# miniE_arduino_shield_v1-3.net
KiCad netlist of a schematic drawn in EAGLE
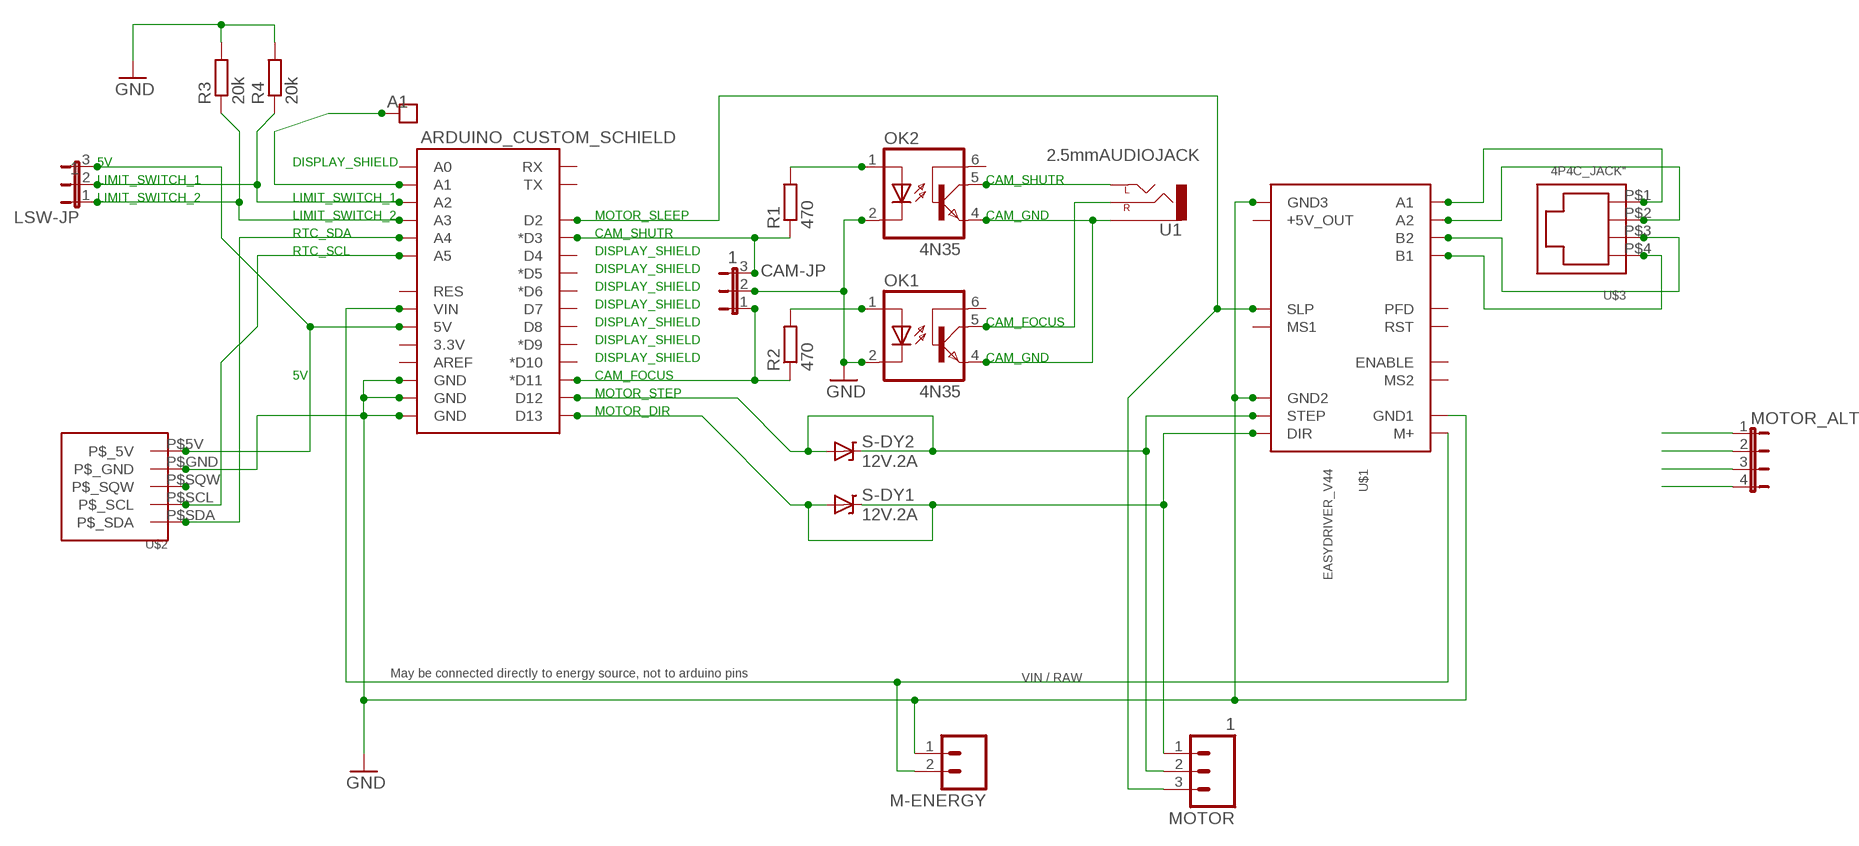
[diagram p0: schematic, sheet 1]

(export (version "E")
  (design (tool "Eeschema 10.0.6"))
  (components
    (comp (ref "ARDUINO_CUSTOM_SCHIELD")
      (value "ARDUINO_SHIELDNOLABELS")
      (footprint "eagle-import:DUEMILANOVE_SHIELD_NOLABELS")
      (libsource (lib "eagle-import") (part "ARDUINO_SHIELDNOLABELS"))
    )
    (comp (ref "CAM-JP")
      (value "1")
      (footprint "eagle-import:JP2")
      (libsource (lib "eagle-import") (part "JP2E"))
    )
    (comp (ref "LSW-JP")
      (value "1")
      (footprint "eagle-import:JP2")
      (libsource (lib "eagle-import") (part "JP2E"))
    )
    (comp (ref "M-ENERGY")
      (value "MOLEX_02")
      (footprint "eagle-import:1X02")
      (libsource (lib "eagle-import") (part "M02PTH"))
    )
    (comp (ref "MOTOR")
      (value "1")
      (footprint "eagle-import:1X03")
      (libsource (lib "eagle-import") (part "M03PTH"))
    )
    (comp (ref "MOTOR_ALT")
      (value "JP4E")
      (footprint "eagle-import:JP4")
      (libsource (lib "eagle-import") (part "JP4E"))
    )
    (comp (ref "OK1")
      (value "4N35")
      (footprint "eagle-import:DIL06")
      (fields (field (name "MF") "FAIRCHILD SEMICONDUCTOR"))
      (libsource (lib "eagle-import") (part "4N35"))
    )
    (comp (ref "OK2")
      (value "4N35")
      (footprint "eagle-import:DIL06")
      (fields (field (name "MF") "FAIRCHILD SEMICONDUCTOR"))
      (libsource (lib "eagle-import") (part "4N35"))
    )
    (comp (ref "R1")
      (value "470")
      (footprint "eagle-import:0207_10")
      (libsource (lib "eagle-import") (part "R-EU_0207/10"))
    )
    (comp (ref "R2")
      (value "470")
      (footprint "eagle-import:0207_10")
      (libsource (lib "eagle-import") (part "R-EU_0207/10"))
    )
    (comp (ref "R3")
      (value "20k")
      (footprint "eagle-import:0207_10")
      (libsource (lib "eagle-import") (part "R-EU_0207/10"))
    )
    (comp (ref "R4")
      (value "20k")
      (footprint "eagle-import:0207_10")
      (libsource (lib "eagle-import") (part "R-EU_0207/10"))
    )
    (comp (ref "S-DY1")
      (value "12V.2A")
      (footprint "eagle-import:DIODE-ZENER")
      (libsource (lib "eagle-import") (part "DIODE-ZENERPTH"))
    )
    (comp (ref "S-DY2")
      (value "12V.2A")
      (footprint "eagle-import:DIODE-ZENER")
      (libsource (lib "eagle-import") (part "DIODE-ZENERPTH"))
    )
    (comp (ref "U$1")
      (value "EASYDRIVER_V44")
      (footprint "eagle-import:EASYDRIVER_V44")
      (libsource (lib "eagle-import") (part "EASYDRIVER_V44"))
    )
    (comp (ref "U$2")
      (value "SPARKFUN_RTC_MODULE-OPTIONAL")
      (footprint "eagle-import:SPARKFUN_RTC_MODULE_OPTIONAL")
      (libsource (lib "eagle-import") (part "SPARKFUN_RTC_MODULE-OPTIONAL"))
    )
    (comp (ref "U$3")
      (value "4P4C_JACK\"")
      (footprint "eagle-import:4P4C_JACK-ASS-2004-3-4-LP-N-R")
      (libsource (lib "eagle-import") (part "4P4C_JACK{dblquote}"))
    )
    (comp (ref "U$4")
      (value "JUMPER_1X1")
      (footprint "eagle-import:JUMPER_1X1")
      (libsource (lib "eagle-import") (part "JUMPER_1X1"))
    )
    (comp (ref "U1")
      (value "2.5mmAUDIOJACK")
      (footprint "eagle-import:STEREOJACK2.5MM_STEREOJACK2.5MM")
      (libsource (lib "eagle-import") (part "AUDIO-JACK2.5MM"))
    )
  )
  (nets
    (net (code "1") (name "/A1") (class "Default")
      (node (ref "MOTOR_ALT") (pin "1") (pinfunction "1_1") (pintype "passive"))
      (node (ref "U$1") (pin "A1") (pinfunction "A1_A1") (pintype "bidirectional"))
      (node (ref "U$3") (pin "P$1") (pinfunction "P$1_P$1") (pintype "bidirectional"))
    )
    (net (code "2") (name "/A2") (class "Default")
      (node (ref "MOTOR_ALT") (pin "2") (pinfunction "2_2") (pintype "passive"))
      (node (ref "U$1") (pin "A2") (pinfunction "A2_A2") (pintype "bidirectional"))
      (node (ref "U$3") (pin "P$2") (pinfunction "P$2_P$2") (pintype "bidirectional"))
    )
    (net (code "3") (name "/B1") (class "Default")
      (node (ref "MOTOR_ALT") (pin "4") (pinfunction "4_4") (pintype "passive"))
      (node (ref "U$1") (pin "B1") (pinfunction "B1_B1") (pintype "bidirectional"))
      (node (ref "U$3") (pin "P$4") (pinfunction "P$4_P$4") (pintype "bidirectional"))
    )
    (net (code "4") (name "/B2") (class "Default")
      (node (ref "MOTOR_ALT") (pin "3") (pinfunction "3_3") (pintype "passive"))
      (node (ref "U$1") (pin "B2") (pinfunction "B2_B2") (pintype "bidirectional"))
      (node (ref "U$3") (pin "P$3") (pinfunction "P$3_P$3") (pintype "bidirectional"))
    )
    (net (code "5") (name "GND") (class "Default")
      (node (ref "ARDUINO_CUSTOM_SCHIELD") (pin "GND@0") (pinfunction "GND_GND@0") (pintype "bidirectional"))
      (node (ref "ARDUINO_CUSTOM_SCHIELD") (pin "GND@1") (pinfunction "GND_GND@1") (pintype "bidirectional"))
      (node (ref "ARDUINO_CUSTOM_SCHIELD") (pin "GND@2") (pinfunction "GND_GND@2") (pintype "bidirectional"))
      (node (ref "CAM-JP") (pin "2") (pinfunction "2_2") (pintype "passive"))
      (node (ref "M-ENERGY") (pin "1") (pinfunction "1_1") (pintype "passive"))
      (node (ref "OK1") (pin "2") (pinfunction "C_2") (pintype "passive"))
      (node (ref "OK2") (pin "2") (pinfunction "C_2") (pintype "passive"))
      (node (ref "R3") (pin "2") (pinfunction "2_2") (pintype "passive"))
      (node (ref "R4") (pin "2") (pinfunction "2_2") (pintype "passive"))
      (node (ref "U$1") (pin "GND1") (pinfunction "GND1_GND1") (pintype "bidirectional"))
      (node (ref "U$1") (pin "GND2") (pinfunction "GND2_GND2") (pintype "bidirectional"))
      (node (ref "U$1") (pin "GND3") (pinfunction "GND3_GND3") (pintype "bidirectional"))
      (node (ref "U$2") (pin "P$GND") (pinfunction "P$_GND_P$GND") (pintype "bidirectional"))
    )
    (net (code "6") (name "Net-(ARDUINO_CUSTOM_SCHIELD-*D3)") (class "Default")
      (node (ref "ARDUINO_CUSTOM_SCHIELD") (pin "D3") (pinfunction "*D3_D3") (pintype "bidirectional"))
      (node (ref "CAM-JP") (pin "3") (pinfunction "3_3") (pintype "passive"))
      (node (ref "R1") (pin "1") (pinfunction "1_1") (pintype "passive"))
    )
    (net (code "7") (name "Net-(ARDUINO_CUSTOM_SCHIELD-*D11)") (class "Default")
      (node (ref "ARDUINO_CUSTOM_SCHIELD") (pin "D11") (pinfunction "*D11_D11") (pintype "bidirectional"))
      (node (ref "CAM-JP") (pin "1") (pinfunction "1_1") (pintype "passive"))
      (node (ref "R2") (pin "1") (pinfunction "1_1") (pintype "passive"))
    )
    (net (code "8") (name "Net-(ARDUINO_CUSTOM_SCHIELD-PadA1)") (class "Default")
      (node (ref "ARDUINO_CUSTOM_SCHIELD") (pin "A1") (pinfunction "A1_A1") (pintype "bidirectional"))
      (node (ref "U$4") (pin "P$1") (pinfunction "P$1_P$1") (pintype "bidirectional"))
    )
    (net (code "9") (name "Net-(ARDUINO_CUSTOM_SCHIELD-PadA2)") (class "Default")
      (node (ref "ARDUINO_CUSTOM_SCHIELD") (pin "A2") (pinfunction "A2_A2") (pintype "bidirectional"))
      (node (ref "LSW-JP") (pin "2") (pinfunction "2_2") (pintype "passive"))
      (node (ref "R4") (pin "1") (pinfunction "1_1") (pintype "passive"))
    )
    (net (code "10") (name "Net-(ARDUINO_CUSTOM_SCHIELD-PadA3)") (class "Default")
      (node (ref "ARDUINO_CUSTOM_SCHIELD") (pin "A3") (pinfunction "A3_A3") (pintype "bidirectional"))
      (node (ref "LSW-JP") (pin "1") (pinfunction "1_1") (pintype "passive"))
      (node (ref "R3") (pin "1") (pinfunction "1_1") (pintype "passive"))
    )
    (net (code "11") (name "Net-(ARDUINO_CUSTOM_SCHIELD-PadVIN)") (class "Default")
      (node (ref "ARDUINO_CUSTOM_SCHIELD") (pin "VIN") (pinfunction "VIN_VIN") (pintype "bidirectional"))
      (node (ref "M-ENERGY") (pin "2") (pinfunction "2_2") (pintype "passive"))
      (node (ref "U$1") (pin "M+") (pinfunction "M+_M+") (pintype "bidirectional"))
    )
    (net (code "12") (name "Net-(OK1-A)") (class "Default")
      (node (ref "OK1") (pin "1") (pinfunction "A_1") (pintype "passive"))
      (node (ref "R2") (pin "2") (pinfunction "2_2") (pintype "passive"))
    )
    (net (code "13") (name "Net-(OK1-COL)") (class "Default")
      (node (ref "OK1") (pin "5") (pinfunction "COL_5") (pintype "passive"))
      (node (ref "U1") (pin "RING1") (pinfunction "RIGHT_RING1") (pintype "bidirectional"))
      (node (ref "U1") (pin "RING2") (pinfunction "RIGHT_RING2") (pintype "bidirectional"))
    )
    (net (code "14") (name "Net-(OK1-EMI)") (class "Default")
      (node (ref "OK1") (pin "4") (pinfunction "EMI_4") (pintype "passive"))
      (node (ref "OK2") (pin "4") (pinfunction "EMI_4") (pintype "passive"))
      (node (ref "U1") (pin "SLEEVE") (pinfunction "SLEEVE_SLEEVE") (pintype "bidirectional"))
    )
    (net (code "15") (name "Net-(OK2-A)") (class "Default")
      (node (ref "OK2") (pin "1") (pinfunction "A_1") (pintype "passive"))
      (node (ref "R1") (pin "2") (pinfunction "2_2") (pintype "passive"))
    )
    (net (code "16") (name "Net-(OK2-COL)") (class "Default")
      (node (ref "OK2") (pin "5") (pinfunction "COL_5") (pintype "passive"))
      (node (ref "U1") (pin "TIP") (pinfunction "LEFT_TIP") (pintype "bidirectional"))
    )
    (net (code "17") (name "Net-(S-DY1-A)") (class "Default")
      (node (ref "ARDUINO_CUSTOM_SCHIELD") (pin "D13") (pinfunction "D13_D13") (pintype "bidirectional"))
      (node (ref "MOTOR") (pin "1") (pinfunction "1_1") (pintype "passive"))
      (node (ref "S-DY1") (pin "P$1") (pinfunction "C_P$1") (pintype "passive"))
      (node (ref "S-DY1") (pin "P$2") (pinfunction "A_P$2") (pintype "passive"))
      (node (ref "U$1") (pin "DIR") (pinfunction "DIR_DIR") (pintype "bidirectional"))
    )
    (net (code "18") (name "Net-(S-DY2-A)") (class "Default")
      (node (ref "ARDUINO_CUSTOM_SCHIELD") (pin "D12") (pinfunction "D12_D12") (pintype "bidirectional"))
      (node (ref "MOTOR") (pin "2") (pinfunction "2_2") (pintype "passive"))
      (node (ref "S-DY2") (pin "P$1") (pinfunction "C_P$1") (pintype "passive"))
      (node (ref "S-DY2") (pin "P$2") (pinfunction "A_P$2") (pintype "passive"))
      (node (ref "U$1") (pin "STEP") (pinfunction "STEP_STEP") (pintype "bidirectional"))
    )
    (net (code "19") (name "Net-(U$1-SLP)") (class "Default")
      (node (ref "ARDUINO_CUSTOM_SCHIELD") (pin "D2") (pinfunction "D2_D2") (pintype "bidirectional"))
      (node (ref "MOTOR") (pin "3") (pinfunction "3_3") (pintype "passive"))
      (node (ref "U$1") (pin "SLEEP") (pinfunction "SLP_SLEEP") (pintype "bidirectional"))
    )
    (net (code "20") (name "Net-(U$2-P$_5V)") (class "Default")
      (node (ref "ARDUINO_CUSTOM_SCHIELD") (pin "5V") (pinfunction "5V_5V") (pintype "bidirectional"))
      (node (ref "LSW-JP") (pin "3") (pinfunction "3_3") (pintype "passive"))
      (node (ref "U$2") (pin "P$5V") (pinfunction "P$_5V_P$5V") (pintype "bidirectional"))
    )
    (net (code "21") (name "Net-(U$2-P$_SCL)") (class "Default")
      (node (ref "ARDUINO_CUSTOM_SCHIELD") (pin "A5") (pinfunction "A5_A5") (pintype "bidirectional"))
      (node (ref "U$2") (pin "P$SCL") (pinfunction "P$_SCL_P$SCL") (pintype "bidirectional"))
    )
    (net (code "22") (name "Net-(U$2-P$_SDA)") (class "Default")
      (node (ref "ARDUINO_CUSTOM_SCHIELD") (pin "A4") (pinfunction "A4_A4") (pintype "bidirectional"))
      (node (ref "U$2") (pin "P$SDA") (pinfunction "P$_SDA_P$SDA") (pintype "bidirectional"))
    )
    (net (code "23") (name "unconnected-(ARDUINO_CUSTOM_SCHIELD-*D5-PadD5)") (class "Default")
      (node (ref "ARDUINO_CUSTOM_SCHIELD") (pin "D5") (pinfunction "*D5_D5") (pintype "bidirectional"))
    )
    (net (code "24") (name "unconnected-(ARDUINO_CUSTOM_SCHIELD-*D6-PadD6)") (class "Default")
      (node (ref "ARDUINO_CUSTOM_SCHIELD") (pin "D6") (pinfunction "*D6_D6") (pintype "bidirectional"))
    )
    (net (code "25") (name "unconnected-(ARDUINO_CUSTOM_SCHIELD-*D9-PadD9)") (class "Default")
      (node (ref "ARDUINO_CUSTOM_SCHIELD") (pin "D9") (pinfunction "*D9_D9") (pintype "bidirectional"))
    )
    (net (code "26") (name "unconnected-(ARDUINO_CUSTOM_SCHIELD-*D10-PadD10)") (class "Default")
      (node (ref "ARDUINO_CUSTOM_SCHIELD") (pin "D10") (pinfunction "*D10_D10") (pintype "bidirectional"))
    )
    (net (code "27") (name "unconnected-(ARDUINO_CUSTOM_SCHIELD-Pad3.3V)") (class "Default")
      (node (ref "ARDUINO_CUSTOM_SCHIELD") (pin "3.3V") (pinfunction "3.3V_3.3V") (pintype "bidirectional"))
    )
    (net (code "28") (name "unconnected-(ARDUINO_CUSTOM_SCHIELD-PadA0)") (class "Default")
      (node (ref "ARDUINO_CUSTOM_SCHIELD") (pin "A0") (pinfunction "A0_A0") (pintype "bidirectional"))
    )
    (net (code "29") (name "unconnected-(ARDUINO_CUSTOM_SCHIELD-PadAREF)") (class "Default")
      (node (ref "ARDUINO_CUSTOM_SCHIELD") (pin "AREF") (pinfunction "AREF_AREF") (pintype "bidirectional"))
    )
    (net (code "30") (name "unconnected-(ARDUINO_CUSTOM_SCHIELD-PadD4)") (class "Default")
      (node (ref "ARDUINO_CUSTOM_SCHIELD") (pin "D4") (pinfunction "D4_D4") (pintype "bidirectional"))
    )
    (net (code "31") (name "unconnected-(ARDUINO_CUSTOM_SCHIELD-PadD7)") (class "Default")
      (node (ref "ARDUINO_CUSTOM_SCHIELD") (pin "D7") (pinfunction "D7_D7") (pintype "bidirectional"))
    )
    (net (code "32") (name "unconnected-(ARDUINO_CUSTOM_SCHIELD-PadD8)") (class "Default")
      (node (ref "ARDUINO_CUSTOM_SCHIELD") (pin "D8") (pinfunction "D8_D8") (pintype "bidirectional"))
    )
    (net (code "33") (name "unconnected-(ARDUINO_CUSTOM_SCHIELD-PadRES)") (class "Default")
      (node (ref "ARDUINO_CUSTOM_SCHIELD") (pin "RES") (pinfunction "RES_RES") (pintype "bidirectional"))
    )
    (net (code "34") (name "unconnected-(ARDUINO_CUSTOM_SCHIELD-PadRX)") (class "Default")
      (node (ref "ARDUINO_CUSTOM_SCHIELD") (pin "RX") (pinfunction "RX_RX") (pintype "bidirectional"))
    )
    (net (code "35") (name "unconnected-(ARDUINO_CUSTOM_SCHIELD-PadTX)") (class "Default")
      (node (ref "ARDUINO_CUSTOM_SCHIELD") (pin "TX") (pinfunction "TX_TX") (pintype "bidirectional"))
    )
    (net (code "36") (name "unconnected-(OK1-BAS-Pad6)") (class "Default")
      (node (ref "OK1") (pin "6") (pinfunction "BAS_6") (pintype "passive"))
    )
    (net (code "37") (name "unconnected-(OK2-BAS-Pad6)") (class "Default")
      (node (ref "OK2") (pin "6") (pinfunction "BAS_6") (pintype "passive"))
    )
    (net (code "38") (name "unconnected-(U$1-+5V_OUT-PadP$11)") (class "Default")
      (node (ref "U$1") (pin "P$11") (pinfunction "+5V_OUT_P$11") (pintype "bidirectional"))
    )
    (net (code "39") (name "unconnected-(U$1-PadENABLE)") (class "Default")
      (node (ref "U$1") (pin "ENABLE") (pinfunction "ENABLE_ENABLE") (pintype "bidirectional"))
    )
    (net (code "40") (name "unconnected-(U$1-PadMS1)") (class "Default")
      (node (ref "U$1") (pin "MS1") (pinfunction "MS1_MS1") (pintype "bidirectional"))
    )
    (net (code "41") (name "unconnected-(U$1-PadMS2)") (class "Default")
      (node (ref "U$1") (pin "MS2") (pinfunction "MS2_MS2") (pintype "bidirectional"))
    )
    (net (code "42") (name "unconnected-(U$1-PadPFD)") (class "Default")
      (node (ref "U$1") (pin "PFD") (pinfunction "PFD_PFD") (pintype "bidirectional"))
    )
    (net (code "43") (name "unconnected-(U$1-PadRST)") (class "Default")
      (node (ref "U$1") (pin "RST") (pinfunction "RST_RST") (pintype "bidirectional"))
    )
    (net (code "44") (name "unconnected-(U$2-P$_SQW-PadP$SQW)") (class "Default")
      (node (ref "U$2") (pin "P$SQW") (pinfunction "P$_SQW_P$SQW") (pintype "bidirectional"))
    )
  )
)
